# Stepper.net
KiCad netlist of a schematic drawn in Altium Designer
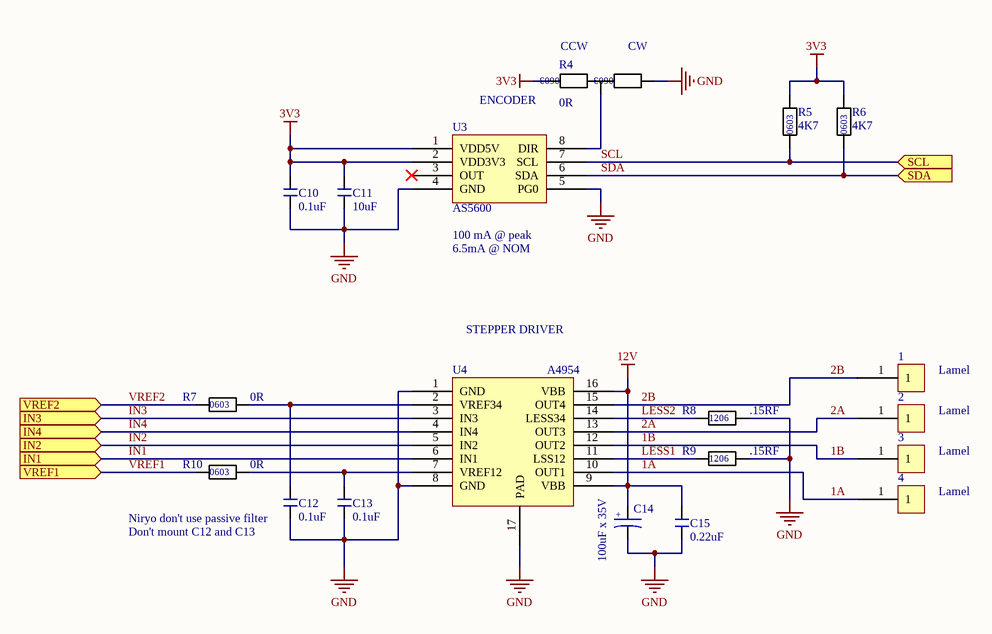
[diagram p0: Stepper.SchDoc]

(export (version "E")
  (design (tool "Eeschema 10.0.6"))
  (components
    (comp (ref "1") (value "Lamel") (footprint "LAMEL") (libsource (lib "Popular") (part "Lamel")))
    (comp (ref "2") (value "Lamel") (footprint "LAMEL") (libsource (lib "Popular") (part "Lamel")))
    (comp (ref "3") (value "Lamel") (footprint "LAMEL") (libsource (lib "Popular") (part "Lamel")))
    (comp (ref "4") (value "Lamel") (footprint "LAMEL") (libsource (lib "Popular") (part "Lamel")))
    (comp (ref "C10") (value "0.1uF") (footprint "CHIP_C_0603") (libsource (lib "Popular") (part "CHIP_C")))
    (comp (ref "C11") (value "10uF") (footprint "CHIP_C_0603") (libsource (lib "Popular") (part "CHIP_C")))
    (comp (ref "C12") (value "0.1uF") (footprint "CHIP_C_0603") (libsource (lib "Popular") (part "CHIP_C")))
    (comp (ref "C13") (value "0.1uF") (footprint "CHIP_C_0603") (libsource (lib "Popular") (part "CHIP_C")))
    (comp (ref "C14")
      (value "100uF x 35V")
      (footprint "ALUM_CAP_D")
      (libsource (lib "Popular") (part "Electrolit"))
    )
    (comp (ref "C15") (value "0.22uF") (footprint "CHIP_C_0603") (libsource (lib "Popular") (part "CHIP_C")))
    (comp (ref "R4")
      (value "0R")
      (footprint "0R 0603 selector")
      (libsource (lib "Popular") (part "Selector_0603"))
    )
    (comp (ref "R5") (value "4K7") (footprint "CHIP_R_0603") (libsource (lib "Popular") (part "RES_0603")))
    (comp (ref "R6") (value "4K7") (footprint "CHIP_R_0603") (libsource (lib "Popular") (part "RES_0603")))
    (comp (ref "R7") (value "0R") (footprint "CHIP_R_0603") (libsource (lib "Popular") (part "RES_0603")))
    (comp (ref "R8")
      (value ".15RF")
      (footprint "CHIP_R_1206")
      (description "Resistor")
      (libsource (lib "Popular") (part "RES_1206"))
    )
    (comp (ref "R9")
      (value ".15RF")
      (footprint "CHIP_R_1206")
      (description "Resistor")
      (libsource (lib "Popular") (part "RES_1206"))
    )
    (comp (ref "R10") (value "0R") (footprint "CHIP_R_0603") (libsource (lib "Popular") (part "RES_0603")))
    (comp (ref "U3")
      (value "AS5600")
      (footprint "SOIC8")
      (description "program magnetic rotary position  sensor")
      (libsource (lib "Popular") (part "AS5600"))
    )
    (comp (ref "U4")
      (value "A4954")
      (footprint "TSSOP-16P")
      (description "DMOS PWM Motor Driver")
      (libsource (lib "Popular") (part "A4954"))
    )
  )
  (nets
    (net (code "1") (name "/1A") (class "Default")
      (node (ref "4") (pin "1") (pinfunction "1_1") (pintype "passive"))
      (node (ref "U4") (pin "10") (pinfunction "OUT1_10") (pintype "passive"))
    )
    (net (code "2") (name "/1B") (class "Default")
      (node (ref "3") (pin "1") (pinfunction "1_1") (pintype "passive"))
      (node (ref "U4") (pin "12") (pinfunction "OUT2_12") (pintype "passive"))
    )
    (net (code "3") (name "/2A") (class "Default")
      (node (ref "2") (pin "1") (pinfunction "1_1") (pintype "passive"))
      (node (ref "U4") (pin "13") (pinfunction "OUT3_13") (pintype "passive"))
    )
    (net (code "4") (name "/2B") (class "Default")
      (node (ref "1") (pin "1") (pinfunction "1_1") (pintype "passive"))
      (node (ref "U4") (pin "15") (pinfunction "OUT4_15") (pintype "passive"))
    )
    (net (code "5") (name "/IN1") (class "Default")
      (node (ref "U4") (pin "6") (pinfunction "IN1_6") (pintype "passive"))
    )
    (net (code "6") (name "/IN2") (class "Default")
      (node (ref "U4") (pin "5") (pinfunction "IN2_5") (pintype "passive"))
    )
    (net (code "7") (name "/IN3") (class "Default")
      (node (ref "U4") (pin "3") (pinfunction "IN3_3") (pintype "passive"))
    )
    (net (code "8") (name "/IN4") (class "Default")
      (node (ref "U4") (pin "4") (pinfunction "IN4_4") (pintype "passive"))
    )
    (net (code "9") (name "/LESS1") (class "Default")
      (node (ref "R9") (pin "1") (pinfunction "1_1") (pintype "passive"))
      (node (ref "U4") (pin "11") (pinfunction "LSS12_11") (pintype "passive"))
    )
    (net (code "10") (name "/LESS2") (class "Default")
      (node (ref "R8") (pin "1") (pinfunction "1_1") (pintype "passive"))
      (node (ref "U4") (pin "14") (pinfunction "LESS34_14") (pintype "passive"))
    )
    (net (code "11") (name "/SCL") (class "Default")
      (node (ref "R5") (pin "1") (pinfunction "1_1") (pintype "passive"))
      (node (ref "U3") (pin "7") (pinfunction "SCL_7") (pintype "passive"))
    )
    (net (code "12") (name "/SDA") (class "Default")
      (node (ref "R6") (pin "1") (pinfunction "1_1") (pintype "passive"))
      (node (ref "U3") (pin "6") (pinfunction "SDA_6") (pintype "passive"))
    )
    (net (code "13") (name "/VREF1") (class "Default")
      (node (ref "R10") (pin "1") (pinfunction "1_1") (pintype "passive"))
    )
    (net (code "14") (name "/VREF2") (class "Default")
      (node (ref "R7") (pin "1") (pinfunction "1_1") (pintype "passive"))
    )
    (net (code "15") (name "3V3") (class "Default")
      (node (ref "C10") (pin "2") (pinfunction "2_2") (pintype "passive"))
      (node (ref "C11") (pin "2") (pinfunction "2_2") (pintype "passive"))
      (node (ref "R4") (pin "1") (pinfunction "1_1") (pintype "passive"))
      (node (ref "R5") (pin "2") (pinfunction "2_2") (pintype "passive"))
      (node (ref "R6") (pin "2") (pinfunction "2_2") (pintype "passive"))
      (node (ref "U3") (pin "1") (pinfunction "VDD5V_1") (pintype "passive"))
      (node (ref "U3") (pin "2") (pinfunction "VDD3V3_2") (pintype "passive"))
    )
    (net (code "16") (name "12V") (class "Default")
      (node (ref "C14") (pin "2") (pinfunction "2_2") (pintype "passive"))
      (node (ref "C15") (pin "2") (pinfunction "2_2") (pintype "passive"))
      (node (ref "U4") (pin "16") (pinfunction "VBB_16") (pintype "passive"))
      (node (ref "U4") (pin "9") (pinfunction "VBB_9") (pintype "passive"))
    )
    (net (code "17") (name "GND") (class "Default")
      (node (ref "C10") (pin "1") (pinfunction "1_1") (pintype "passive"))
      (node (ref "C11") (pin "1") (pinfunction "1_1") (pintype "passive"))
      (node (ref "C12") (pin "1") (pinfunction "1_1") (pintype "passive"))
      (node (ref "C13") (pin "1") (pinfunction "1_1") (pintype "passive"))
      (node (ref "C14") (pin "1") (pinfunction "1_1") (pintype "passive"))
      (node (ref "C15") (pin "1") (pinfunction "1_1") (pintype "passive"))
      (node (ref "R4") (pin "3") (pinfunction "3_3") (pintype "passive"))
      (node (ref "R8") (pin "2") (pinfunction "2_2") (pintype "passive"))
      (node (ref "R9") (pin "2") (pinfunction "2_2") (pintype "passive"))
      (node (ref "U3") (pin "4") (pinfunction "GND_4") (pintype "passive"))
      (node (ref "U3") (pin "5") (pinfunction "PG0_5") (pintype "passive"))
      (node (ref "U4") (pin "1") (pinfunction "GND_1") (pintype "passive"))
      (node (ref "U4") (pin "17") (pinfunction "PAD_17") (pintype "passive"))
      (node (ref "U4") (pin "8") (pinfunction "GND_8") (pintype "passive"))
    )
    (net (code "18") (name "Net-(U3-DIR)") (class "Default")
      (node (ref "R4") (pin "2") (pinfunction "2_2") (pintype "passive"))
      (node (ref "U3") (pin "8") (pinfunction "DIR_8") (pintype "passive"))
    )
    (net (code "19") (name "Net-(U4-VREF12)") (class "Default")
      (node (ref "C13") (pin "2") (pinfunction "2_2") (pintype "passive"))
      (node (ref "R10") (pin "2") (pinfunction "2_2") (pintype "passive"))
      (node (ref "U4") (pin "7") (pinfunction "VREF12_7") (pintype "passive"))
    )
    (net (code "20") (name "Net-(U4-VREF34)") (class "Default")
      (node (ref "C12") (pin "2") (pinfunction "2_2") (pintype "passive"))
      (node (ref "R7") (pin "2") (pinfunction "2_2") (pintype "passive"))
      (node (ref "U4") (pin "2") (pinfunction "VREF34_2") (pintype "passive"))
    )
    (net (code "21") (name "unconnected-(U3-OUT-Pad3)") (class "Default")
      (node (ref "U3") (pin "3") (pinfunction "OUT_3") (pintype "passive+no_connect"))
    )
  )
)
